# digAudio-PLT133.net
KiCad netlist of a schematic drawn in EAGLE
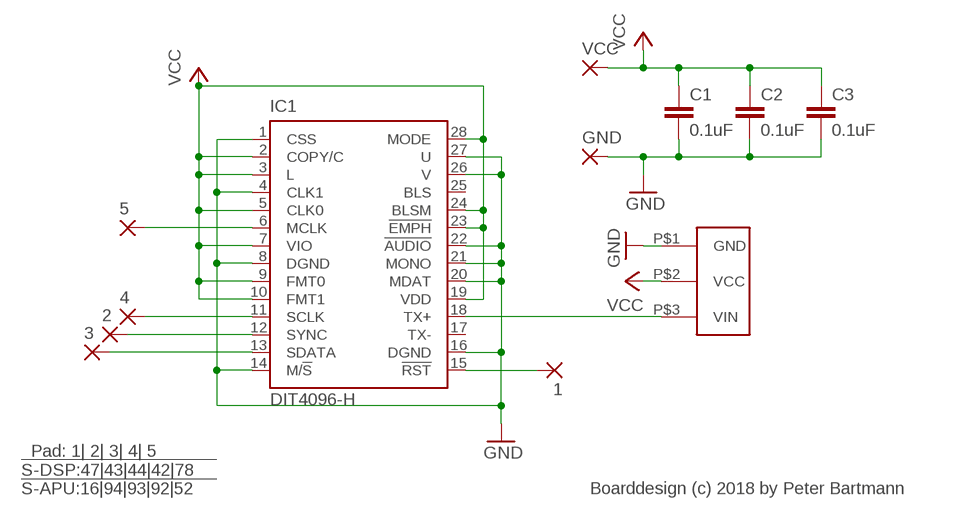
[diagram p0: schematic, sheet 1]

(export (version "E")
  (design (tool "Eeschema 10.0.6"))
  (components
    (comp (ref "1")
      (value "SMD1")
      (footprint "eagle-import:SMD0,8-1,6")
      (libsource (lib "eagle-import") (part "SMD1"))
    )
    (comp (ref "2")
      (value "SMD1")
      (footprint "eagle-import:SMD0,8-1,6")
      (libsource (lib "eagle-import") (part "SMD1"))
    )
    (comp (ref "3")
      (value "SMD1")
      (footprint "eagle-import:SMD0,8-1,6")
      (libsource (lib "eagle-import") (part "SMD1"))
    )
    (comp (ref "4")
      (value "SMD1")
      (footprint "eagle-import:SMD0,8-1,6")
      (libsource (lib "eagle-import") (part "SMD1"))
    )
    (comp (ref "5")
      (value "SMD1")
      (footprint "eagle-import:SMD0,8-1,6")
      (libsource (lib "eagle-import") (part "SMD1"))
    )
    (comp (ref "C1")
      (value "0.1uF")
      (footprint "eagle-import:C0603")
      (libsource (lib "eagle-import") (part "C-EUC0603"))
    )
    (comp (ref "C2")
      (value "0.1uF")
      (footprint "eagle-import:C0603")
      (libsource (lib "eagle-import") (part "C-EUC0603"))
    )
    (comp (ref "C3")
      (value "0.1uF")
      (footprint "eagle-import:C0603")
      (libsource (lib "eagle-import") (part "C-EUC0603"))
    )
    (comp (ref "GND")
      (value "SMD2")
      (footprint "eagle-import:SMD1,27-2,54")
      (libsource (lib "eagle-import") (part "SMD2"))
    )
    (comp (ref "IC1")
      (value "DIT4096-H")
      (footprint "eagle-import:PW_R-PDSO-G28")
      (fields (field (name "MF") "TEXAS INSTRUMENTS") (field (name "MPN") "DIT4192IPW"))
      (libsource (lib "eagle-import") (part "DIT4192-H"))
    )
    (comp (ref "U$1")
      (value "PLT133/T10W")
      (footprint "eagle-import:PLT133_T10W")
      (libsource (lib "eagle-import") (part "PLT133/T10W"))
    )
    (comp (ref "VCC")
      (value "SMD2")
      (footprint "eagle-import:SMD1,27-2,54")
      (libsource (lib "eagle-import") (part "SMD2"))
    )
  )
  (nets
    (net (code "1") (name "GND") (class "Default")
      (node (ref "C1") (pin "2") (pinfunction "2_2") (pintype "passive"))
      (node (ref "C2") (pin "2") (pinfunction "2_2") (pintype "passive"))
      (node (ref "C3") (pin "2") (pinfunction "2_2") (pintype "passive"))
      (node (ref "GND") (pin "1") (pinfunction "P_1") (pintype "passive"))
      (node (ref "IC1") (pin "1") (pinfunction "CSS_1") (pintype "input"))
      (node (ref "IC1") (pin "14") (pinfunction "M/~{S}_14") (pintype "input"))
      (node (ref "IC1") (pin "16") (pinfunction "DGND_16") (pintype "power_in"))
      (node (ref "IC1") (pin "20") (pinfunction "MDAT_20") (pintype "input"))
      (node (ref "IC1") (pin "21") (pinfunction "MONO_21") (pintype "input"))
      (node (ref "IC1") (pin "22") (pinfunction "~{AUDIO}_22") (pintype "input"))
      (node (ref "IC1") (pin "26") (pinfunction "V_26") (pintype "input"))
      (node (ref "IC1") (pin "27") (pinfunction "U_27") (pintype "input"))
      (node (ref "IC1") (pin "4") (pinfunction "CLK1_4") (pintype "input"))
      (node (ref "IC1") (pin "8") (pinfunction "DGND_8") (pintype "power_in"))
      (node (ref "U$1") (pin "P$1") (pinfunction "GND_P$1") (pintype "bidirectional"))
    )
    (net (code "2") (name "Net-(1-P)") (class "Default")
      (node (ref "1") (pin "P$1") (pinfunction "P_P$1") (pintype "passive"))
      (node (ref "IC1") (pin "15") (pinfunction "~{RST}_15") (pintype "input"))
    )
    (net (code "3") (name "Net-(2-P)") (class "Default")
      (node (ref "2") (pin "P$1") (pinfunction "P_P$1") (pintype "passive"))
      (node (ref "IC1") (pin "12") (pinfunction "SYNC_12") (pintype "bidirectional"))
    )
    (net (code "4") (name "Net-(3-P)") (class "Default")
      (node (ref "3") (pin "P$1") (pinfunction "P_P$1") (pintype "passive"))
      (node (ref "IC1") (pin "13") (pinfunction "SDATA_13") (pintype "input"))
    )
    (net (code "5") (name "Net-(4-P)") (class "Default")
      (node (ref "4") (pin "P$1") (pinfunction "P_P$1") (pintype "passive"))
      (node (ref "IC1") (pin "11") (pinfunction "SCLK_11") (pintype "bidirectional"))
    )
    (net (code "6") (name "Net-(5-P)") (class "Default")
      (node (ref "5") (pin "P$1") (pinfunction "P_P$1") (pintype "passive"))
      (node (ref "IC1") (pin "6") (pinfunction "MCLK_6") (pintype "input"))
    )
    (net (code "7") (name "Net-(IC1-TX+)") (class "Default")
      (node (ref "IC1") (pin "18") (pinfunction "TX+_18") (pintype "output"))
      (node (ref "U$1") (pin "P$3") (pinfunction "VIN_P$3") (pintype "bidirectional"))
    )
    (net (code "8") (name "VCC") (class "Default")
      (node (ref "C1") (pin "1") (pinfunction "1_1") (pintype "passive"))
      (node (ref "C2") (pin "1") (pinfunction "1_1") (pintype "passive"))
      (node (ref "C3") (pin "1") (pinfunction "1_1") (pintype "passive"))
      (node (ref "IC1") (pin "10") (pinfunction "FMT1_10") (pintype "input"))
      (node (ref "IC1") (pin "19") (pinfunction "VDD_19") (pintype "power_in"))
      (node (ref "IC1") (pin "2") (pinfunction "COPY/C_2") (pintype "input"))
      (node (ref "IC1") (pin "23") (pinfunction "~{EMPH}_23") (pintype "input"))
      (node (ref "IC1") (pin "24") (pinfunction "BLSM_24") (pintype "input"))
      (node (ref "IC1") (pin "28") (pinfunction "MODE_28") (pintype "input"))
      (node (ref "IC1") (pin "3") (pinfunction "L_3") (pintype "input"))
      (node (ref "IC1") (pin "5") (pinfunction "CLK0_5") (pintype "input"))
      (node (ref "IC1") (pin "7") (pinfunction "VIO_7") (pintype "power_in"))
      (node (ref "IC1") (pin "9") (pinfunction "FMT0_9") (pintype "input"))
      (node (ref "U$1") (pin "P$2") (pinfunction "VCC_P$2") (pintype "bidirectional"))
      (node (ref "VCC") (pin "1") (pinfunction "P_1") (pintype "passive"))
    )
    (net (code "9") (name "unconnected-(IC1-BLS-Pad25)") (class "Default")
      (node (ref "IC1") (pin "25") (pinfunction "BLS_25") (pintype "bidirectional"))
    )
    (net (code "10") (name "unconnected-(IC1-TX--Pad17)") (class "Default")
      (node (ref "IC1") (pin "17") (pinfunction "TX-_17") (pintype "output"))
    )
  )
)
